# Audio_Cape_Guitar_Conversion.net
KiCad netlist of a schematic drawn in EAGLE
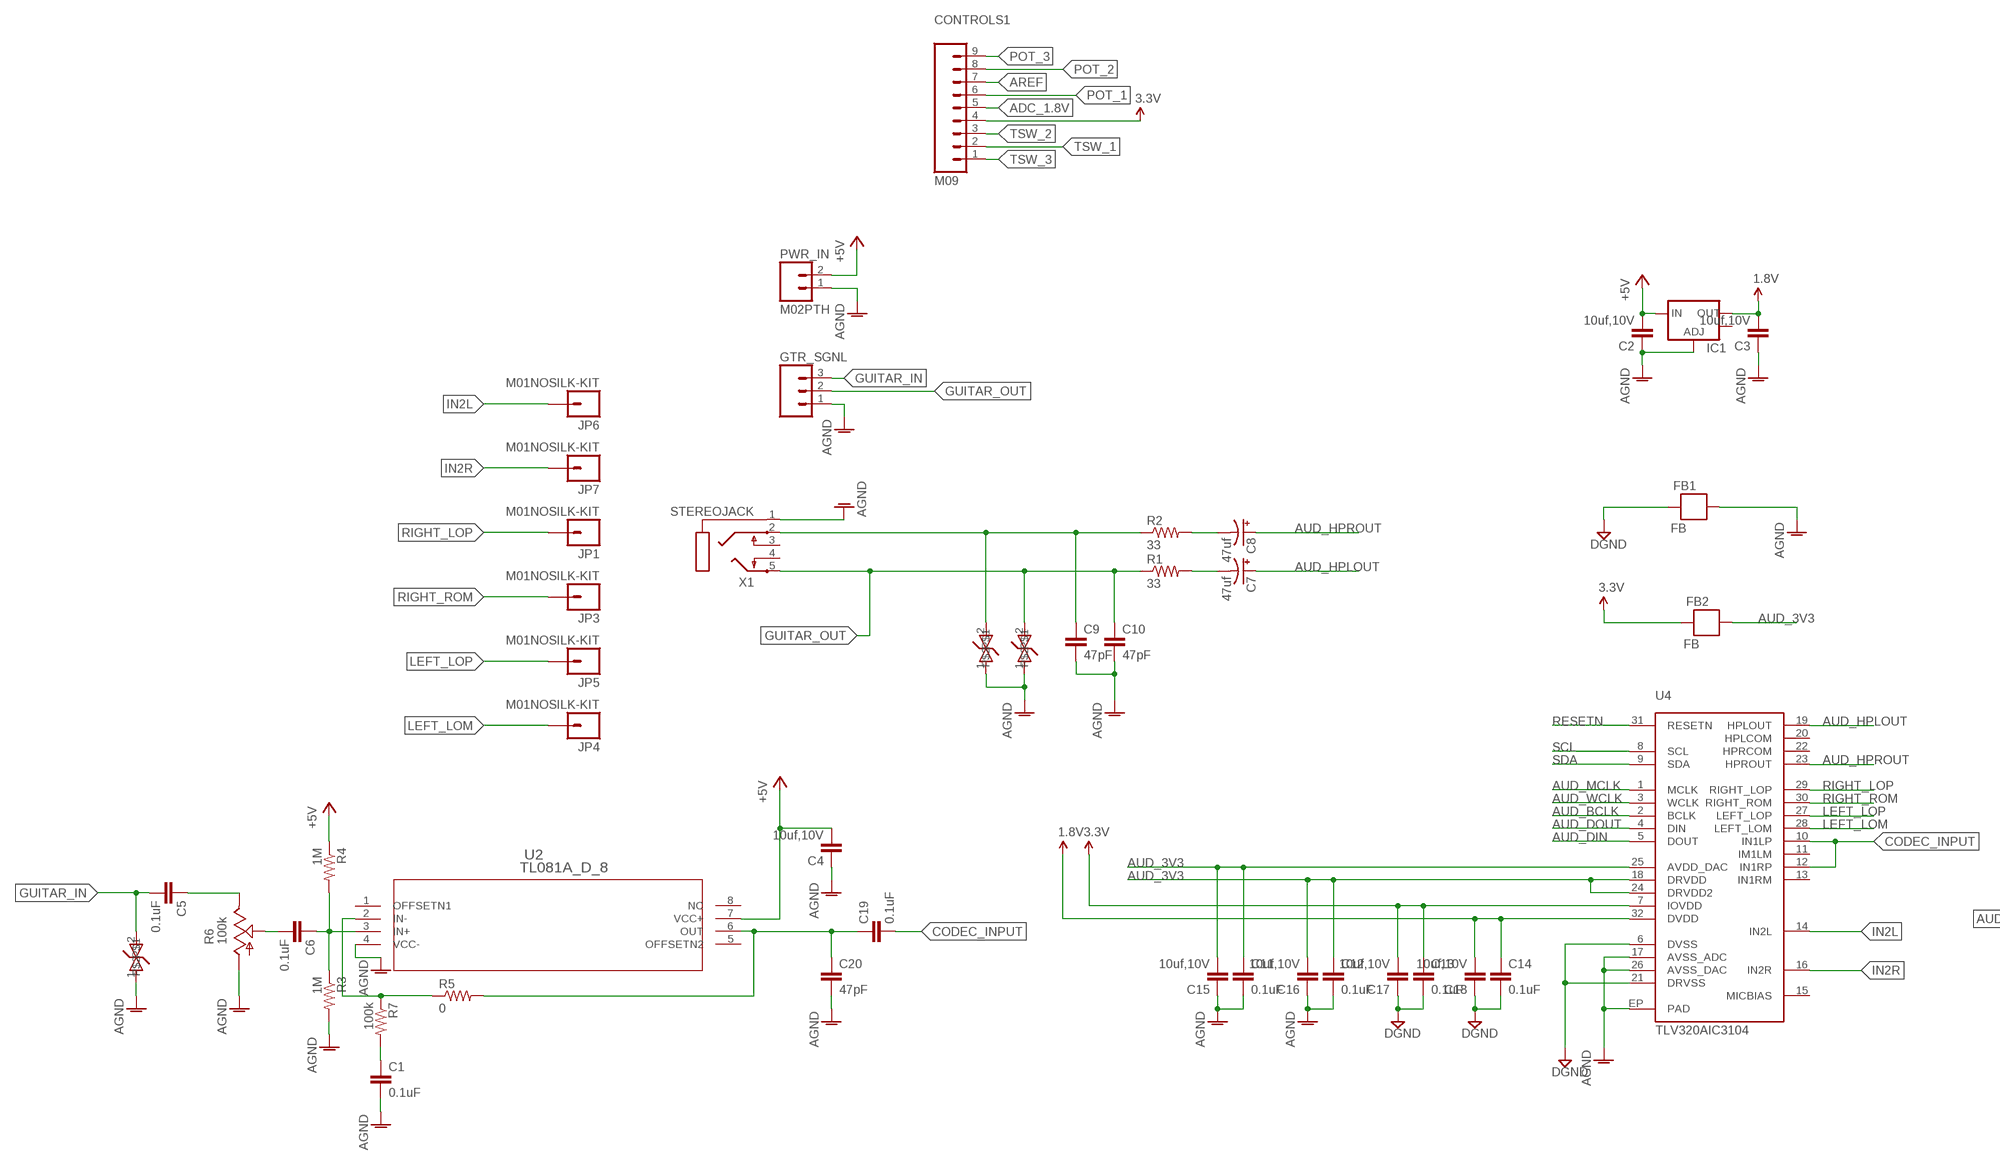
[diagram p0: schematic, sheet 1, part 1 of 2]
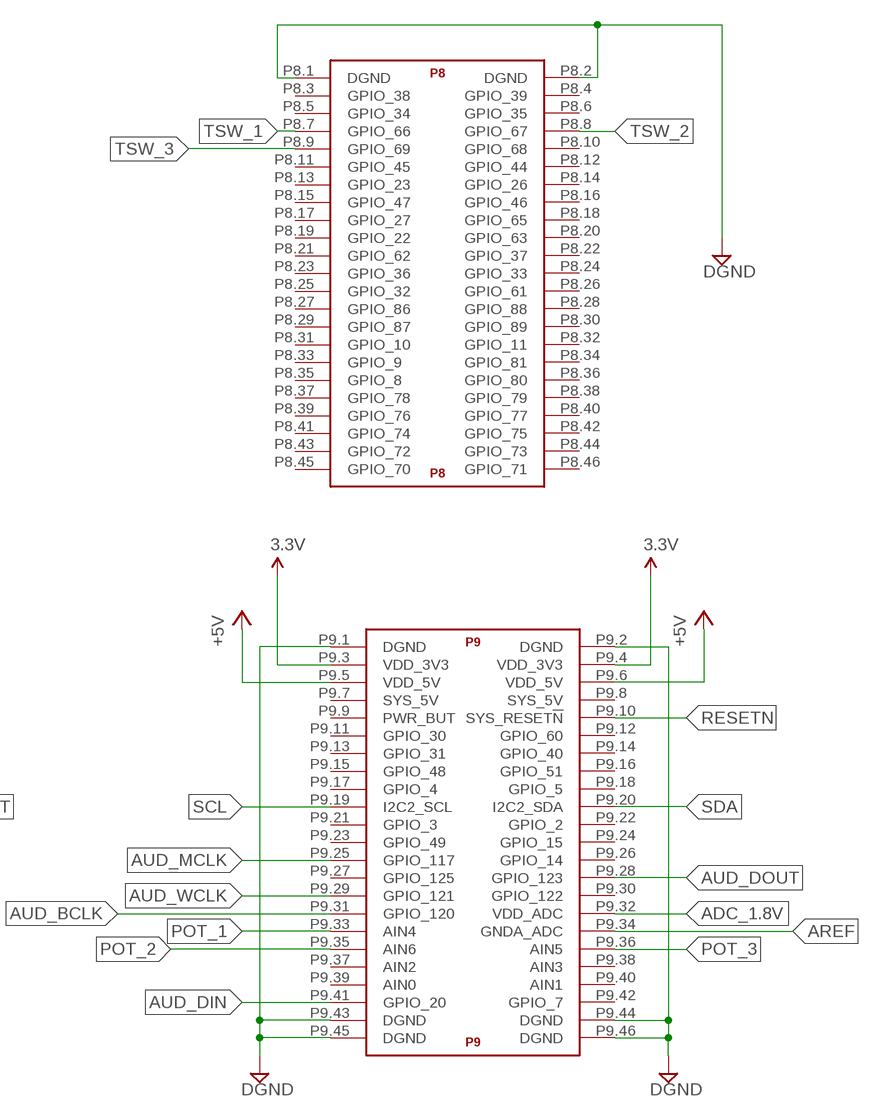
[diagram p1: schematic, sheet 1, part 2 of 2]

(export (version "E")
  (design (tool "Eeschema 10.0.6"))
  (components
    (comp (ref "C1")
      (value "0.1uF")
      (footprint "eagle-import:0603-CAP")
      (libsource (lib "eagle-import") (part "0.1UF-25V-5%(0603)"))
    )
    (comp (ref "C2")
      (value "10uf,10V")
      (footprint "eagle-import:0603-CAP")
      (libsource (lib "eagle-import") (part "CAP0603-CAP"))
    )
    (comp (ref "C3")
      (value "10uf,10V")
      (footprint "eagle-import:0603-CAP")
      (libsource (lib "eagle-import") (part "CAP0603-CAP"))
    )
    (comp (ref "C4")
      (value "10uf,10V")
      (footprint "eagle-import:0603-CAP")
      (libsource (lib "eagle-import") (part "CAP0603-CAP"))
    )
    (comp (ref "C5")
      (value "0.1uF")
      (footprint "eagle-import:0603-CAP")
      (libsource (lib "eagle-import") (part "0.1UF-25V-5%(0603)"))
    )
    (comp (ref "C6")
      (value "0.1uF")
      (footprint "eagle-import:0603-CAP")
      (libsource (lib "eagle-import") (part "0.1UF-25V-5%(0603)"))
    )
    (comp (ref "C7")
      (value "47uf")
      (footprint "eagle-import:EIA3216")
      (libsource (lib "eagle-import") (part "CAP_POL1206"))
    )
    (comp (ref "C8")
      (value "47uf")
      (footprint "eagle-import:EIA3216")
      (libsource (lib "eagle-import") (part "CAP_POL1206"))
    )
    (comp (ref "C9")
      (value "47pF")
      (footprint "eagle-import:0402-CAP")
      (libsource (lib "eagle-import") (part "CAP0402-CAP"))
    )
    (comp (ref "C10")
      (value "47pF")
      (footprint "eagle-import:0402-CAP")
      (libsource (lib "eagle-import") (part "CAP0402-CAP"))
    )
    (comp (ref "C11")
      (value "0.1uF")
      (footprint "eagle-import:0603-CAP")
      (libsource (lib "eagle-import") (part "0.1UF-25V-5%(0603)"))
    )
    (comp (ref "C12")
      (value "0.1uF")
      (footprint "eagle-import:0603-CAP")
      (libsource (lib "eagle-import") (part "0.1UF-25V-5%(0603)"))
    )
    (comp (ref "C13")
      (value "0.1uF")
      (footprint "eagle-import:0603-CAP")
      (libsource (lib "eagle-import") (part "0.1UF-25V-5%(0603)"))
    )
    (comp (ref "C14")
      (value "0.1uF")
      (footprint "eagle-import:0603-CAP")
      (libsource (lib "eagle-import") (part "0.1UF-25V-5%(0603)"))
    )
    (comp (ref "C15")
      (value "10uf,10V")
      (footprint "eagle-import:0603-CAP")
      (libsource (lib "eagle-import") (part "CAP0603-CAP"))
    )
    (comp (ref "C16")
      (value "10uf,10V")
      (footprint "eagle-import:0603-CAP")
      (libsource (lib "eagle-import") (part "CAP0603-CAP"))
    )
    (comp (ref "C17")
      (value "10uf,10V")
      (footprint "eagle-import:0603-CAP")
      (libsource (lib "eagle-import") (part "CAP0603-CAP"))
    )
    (comp (ref "C18")
      (value "10uf,10V")
      (footprint "eagle-import:0603-CAP")
      (libsource (lib "eagle-import") (part "CAP0603-CAP"))
    )
    (comp (ref "C19")
      (value "0.1uF")
      (footprint "eagle-import:0603-CAP")
      (libsource (lib "eagle-import") (part "0.1UF-25V-5%(0603)"))
    )
    (comp (ref "C20")
      (value "47pF")
      (footprint "eagle-import:0402-CAP")
      (libsource (lib "eagle-import") (part "CAP0402-CAP"))
    )
    (comp (ref "CONTROLS1")
      (value "M09")
      (footprint "eagle-import:1X09")
      (libsource (lib "eagle-import") (part "M09"))
    )
    (comp (ref "D1")
      (value "PGB0010603MR")
      (footprint "eagle-import:0603")
      (libsource (lib "eagle-import") (part "PGB0010603MR"))
    )
    (comp (ref "D2")
      (value "PGB0010603MR")
      (footprint "eagle-import:0603")
      (libsource (lib "eagle-import") (part "PGB0010603MR"))
    )
    (comp (ref "D3")
      (value "PGB0010603MR")
      (footprint "eagle-import:0603")
      (libsource (lib "eagle-import") (part "PGB0010603MR"))
    )
    (comp (ref "FB1")
      (value "FB")
      (footprint "eagle-import:0603")
      (libsource (lib "eagle-import") (part "FB"))
    )
    (comp (ref "FB2")
      (value "FB")
      (footprint "eagle-import:0603")
      (libsource (lib "eagle-import") (part "FB"))
    )
    (comp (ref "GTR_SGNL")
      (value "M03PTH")
      (footprint "eagle-import:1X03")
      (libsource (lib "eagle-import") (part "M03PTH"))
    )
    (comp (ref "IC1")
      (value "V_REG_LM1117SOT223")
      (footprint "eagle-import:SOT223")
      (libsource (lib "eagle-import") (part "V_REG_LM1117SOT223"))
    )
    (comp (ref "JP1")
      (value "M01NOSILK-KIT")
      (footprint "eagle-import:1X01NS-KIT")
      (libsource (lib "eagle-import") (part "M01NOSILK-KIT"))
    )
    (comp (ref "JP3")
      (value "M01NOSILK-KIT")
      (footprint "eagle-import:1X01NS-KIT")
      (libsource (lib "eagle-import") (part "M01NOSILK-KIT"))
    )
    (comp (ref "JP4")
      (value "M01NOSILK-KIT")
      (footprint "eagle-import:1X01NS-KIT")
      (libsource (lib "eagle-import") (part "M01NOSILK-KIT"))
    )
    (comp (ref "JP5")
      (value "M01NOSILK-KIT")
      (footprint "eagle-import:1X01NS-KIT")
      (libsource (lib "eagle-import") (part "M01NOSILK-KIT"))
    )
    (comp (ref "JP6")
      (value "M01NOSILK-KIT")
      (footprint "eagle-import:1X01NS-KIT")
      (libsource (lib "eagle-import") (part "M01NOSILK-KIT"))
    )
    (comp (ref "JP7")
      (value "M01NOSILK-KIT")
      (footprint "eagle-import:1X01NS-KIT")
      (libsource (lib "eagle-import") (part "M01NOSILK-KIT"))
    )
    (comp (ref "PWR_IN")
      (value "M02PTH")
      (footprint "eagle-import:1X02")
      (libsource (lib "eagle-import") (part "M02PTH"))
    )
    (comp (ref "R1")
      (value "33")
      (footprint "eagle-import:1206")
      (libsource (lib "eagle-import") (part "SparkFun-Resistors_RESISTOR1206"))
    )
    (comp (ref "R2")
      (value "33")
      (footprint "eagle-import:1206")
      (libsource (lib "eagle-import") (part "SparkFun-Resistors_RESISTOR1206"))
    )
    (comp (ref "R3")
      (value "1M")
      (footprint "eagle-import:1206")
      (libsource (lib "eagle-import") (part "SparkFun-Resistors_RESISTOR1206"))
    )
    (comp (ref "R4")
      (value "1M")
      (footprint "eagle-import:1206")
      (libsource (lib "eagle-import") (part "SparkFun-Resistors_RESISTOR1206"))
    )
    (comp (ref "R5")
      (value "0")
      (footprint "eagle-import:AXIAL-0.4")
      (libsource (lib "eagle-import") (part "RESISTORPTH-1/4W"))
    )
    (comp (ref "R6")
      (value "100k")
      (footprint "eagle-import:S64Y")
      (libsource (lib "eagle-import") (part "TRIM_US-S64Y"))
    )
    (comp (ref "R7")
      (value "100k")
      (footprint "eagle-import:1206")
      (libsource (lib "eagle-import") (part "SparkFun-Resistors_RESISTOR1206"))
    )
    (comp (ref "U$1")
      (value "BEAGLE_BONE_BLACK_CAPE")
      (footprint "eagle-import:BEAGLE_BONE_BLACK_CAPE")
      (libsource (lib "eagle-import") (part "BEAGLE_BONE_BLACK_CAPE"))
    )
    (comp (ref "U2")
      (value "TL081A_D_8")
      (footprint "eagle-import:D8")
      (fields
        (field (name "GENERIC_PART_NUMBER") "TL081A")
        (field (name "MANUFACTURER") "Texas Instruments")
        (field (name "MANUFACTURER_PART_NUMBER") "tl081a_d_8")
      )
      (libsource (lib "eagle-import") (part "TL081A_D_8"))
    )
    (comp (ref "U4")
      (value "TLV320AIC3104")
      (footprint "eagle-import:QFN-32")
      (libsource (lib "eagle-import") (part "TLV320AIC3104"))
    )
    (comp (ref "X1")
      (value "STEREOJACK")
      (footprint "eagle-import:STX3100")
      (libsource (lib "eagle-import") (part "STEREOJACK"))
    )
  )
  (nets
    (net (code "1") (name "+5V") (class "Default")
      (node (ref "C2") (pin "2") (pinfunction "2_2") (pintype "passive"))
      (node (ref "C4") (pin "2") (pinfunction "2_2") (pintype "passive"))
      (node (ref "IC1") (pin "3") (pinfunction "IN_3") (pintype "input"))
      (node (ref "PWR_IN") (pin "2") (pinfunction "2_2") (pintype "passive"))
      (node (ref "R4") (pin "1") (pinfunction "1_1") (pintype "passive"))
      (node (ref "U$1") (pin "P9.5") (pinfunction "VDD_5V_P9.5") (pintype "bidirectional"))
      (node (ref "U$1") (pin "P9.6") (pinfunction "VDD_5V_P9.6") (pintype "bidirectional"))
      (node (ref "U2") (pin "7") (pinfunction "VCC+_7") (pintype "power_in"))
    )
    (net (code "2") (name "/AUD_3V3") (class "Default")
      (node (ref "C11") (pin "1") (pinfunction "1_1") (pintype "passive"))
      (node (ref "C12") (pin "1") (pinfunction "1_1") (pintype "passive"))
      (node (ref "C15") (pin "2") (pinfunction "2_2") (pintype "passive"))
      (node (ref "C16") (pin "2") (pinfunction "2_2") (pintype "passive"))
      (node (ref "FB2") (pin "1") (pinfunction "P$1_1") (pintype "bidirectional"))
      (node (ref "U4") (pin "18") (pinfunction "DRVDD_18") (pintype "bidirectional"))
      (node (ref "U4") (pin "24") (pinfunction "DRVDD2_24") (pintype "bidirectional"))
      (node (ref "U4") (pin "25") (pinfunction "AVDD_DAC_25") (pintype "bidirectional"))
    )
    (net (code "3") (name "/AUD_HPLOUT") (class "Default")
      (node (ref "C7") (pin "A") (pinfunction "+_A") (pintype "passive"))
      (node (ref "U4") (pin "19") (pinfunction "HPLOUT_19") (pintype "bidirectional"))
    )
    (net (code "4") (name "/AUD_HPROUT") (class "Default")
      (node (ref "C8") (pin "A") (pinfunction "+_A") (pintype "passive"))
      (node (ref "U4") (pin "23") (pinfunction "HPROUT_23") (pintype "bidirectional"))
    )
    (net (code "5") (name "1.8V") (class "Default")
      (node (ref "C14") (pin "1") (pinfunction "1_1") (pintype "passive"))
      (node (ref "C18") (pin "2") (pinfunction "2_2") (pintype "passive"))
      (node (ref "C3") (pin "2") (pinfunction "2_2") (pintype "passive"))
      (node (ref "IC1") (pin "2") (pinfunction "OUT_2") (pintype "output"))
      (node (ref "U4") (pin "32") (pinfunction "DVDD_32") (pintype "bidirectional"))
    )
    (net (code "6") (name "3.3V") (class "Default")
      (node (ref "C13") (pin "1") (pinfunction "1_1") (pintype "passive"))
      (node (ref "C17") (pin "2") (pinfunction "2_2") (pintype "passive"))
      (node (ref "CONTROLS1") (pin "4") (pinfunction "4_4") (pintype "passive"))
      (node (ref "FB2") (pin "2") (pinfunction "P$2_2") (pintype "bidirectional"))
      (node (ref "U$1") (pin "P9.3") (pinfunction "VDD_3V3_P9.3") (pintype "bidirectional"))
      (node (ref "U$1") (pin "P9.4") (pinfunction "VDD_3V3_P9.4") (pintype "bidirectional"))
      (node (ref "U4") (pin "7") (pinfunction "IOVDD_7") (pintype "bidirectional"))
    )
    (net (code "7") (name "ADC_1.8V") (class "Default")
      (node (ref "CONTROLS1") (pin "5") (pinfunction "5_5") (pintype "passive"))
      (node (ref "U$1") (pin "P9.32") (pinfunction "VDD_ADC_P9.32") (pintype "bidirectional"))
    )
    (net (code "8") (name "AGND") (class "Default")
      (node (ref "C1") (pin "2") (pinfunction "2_2") (pintype "passive"))
      (node (ref "C10") (pin "2") (pinfunction "2_2") (pintype "passive"))
      (node (ref "C11") (pin "2") (pinfunction "2_2") (pintype "passive"))
      (node (ref "C12") (pin "2") (pinfunction "2_2") (pintype "passive"))
      (node (ref "C15") (pin "1") (pinfunction "1_1") (pintype "passive"))
      (node (ref "C16") (pin "1") (pinfunction "1_1") (pintype "passive"))
      (node (ref "C2") (pin "1") (pinfunction "1_1") (pintype "passive"))
      (node (ref "C20") (pin "2") (pinfunction "2_2") (pintype "passive"))
      (node (ref "C3") (pin "1") (pinfunction "1_1") (pintype "passive"))
      (node (ref "C4") (pin "1") (pinfunction "1_1") (pintype "passive"))
      (node (ref "C9") (pin "2") (pinfunction "2_2") (pintype "passive"))
      (node (ref "D1") (pin "1") (pinfunction "P$1_1") (pintype "bidirectional"))
      (node (ref "D2") (pin "1") (pinfunction "P$1_1") (pintype "bidirectional"))
      (node (ref "D3") (pin "1") (pinfunction "P$1_1") (pintype "bidirectional"))
      (node (ref "FB1") (pin "1") (pinfunction "P$1_1") (pintype "bidirectional"))
      (node (ref "GTR_SGNL") (pin "1") (pinfunction "1_1") (pintype "passive"))
      (node (ref "IC1") (pin "1") (pinfunction "ADJ_1") (pintype "input"))
      (node (ref "PWR_IN") (pin "1") (pinfunction "1_1") (pintype "passive"))
      (node (ref "R3") (pin "2") (pinfunction "2_2") (pintype "passive"))
      (node (ref "R6") (pin "A") (pinfunction "A_A") (pintype "passive"))
      (node (ref "U2") (pin "4") (pinfunction "VCC-_4") (pintype "power_in"))
      (node (ref "U4") (pin "17") (pinfunction "AVSS_ADC_17") (pintype "bidirectional"))
      (node (ref "U4") (pin "26") (pinfunction "AVSS_DAC_26") (pintype "bidirectional"))
      (node (ref "U4") (pin "EP") (pinfunction "PAD_EP") (pintype "bidirectional"))
      (node (ref "X1") (pin "1") (pinfunction "1_1") (pintype "passive"))
    )
    (net (code "9") (name "AREF") (class "Default")
      (node (ref "CONTROLS1") (pin "7") (pinfunction "7_7") (pintype "passive"))
      (node (ref "U$1") (pin "P9.34") (pinfunction "GNDA_ADC_P9.34") (pintype "bidirectional"))
    )
    (net (code "10") (name "AUD_BCLK") (class "Default")
      (node (ref "U$1") (pin "P9.31") (pinfunction "GPIO_120_P9.31") (pintype "bidirectional"))
      (node (ref "U4") (pin "2") (pinfunction "BCLK_2") (pintype "bidirectional"))
    )
    (net (code "11") (name "AUD_DIN") (class "Default")
      (node (ref "U$1") (pin "P9.41") (pinfunction "GPIO_20_P9.41") (pintype "bidirectional"))
      (node (ref "U4") (pin "5") (pinfunction "DOUT_5") (pintype "bidirectional"))
    )
    (net (code "12") (name "AUD_DOUT") (class "Default")
      (node (ref "U$1") (pin "P9.28") (pinfunction "GPIO_123_P9.28") (pintype "bidirectional"))
      (node (ref "U4") (pin "4") (pinfunction "DIN_4") (pintype "bidirectional"))
    )
    (net (code "13") (name "AUD_MCLK") (class "Default")
      (node (ref "U$1") (pin "P9.25") (pinfunction "GPIO_117_P9.25") (pintype "bidirectional"))
      (node (ref "U4") (pin "1") (pinfunction "MCLK_1") (pintype "bidirectional"))
    )
    (net (code "14") (name "AUD_WCLK") (class "Default")
      (node (ref "U$1") (pin "P9.29") (pinfunction "GPIO_121_P9.29") (pintype "bidirectional"))
      (node (ref "U4") (pin "3") (pinfunction "WCLK_3") (pintype "bidirectional"))
    )
    (net (code "15") (name "CODEC_INPUT") (class "Default")
      (node (ref "C19") (pin "2") (pinfunction "2_2") (pintype "passive"))
      (node (ref "U4") (pin "10") (pinfunction "IN1LP_10") (pintype "bidirectional"))
      (node (ref "U4") (pin "12") (pinfunction "IN1RP_12") (pintype "bidirectional"))
    )
    (net (code "16") (name "DGND") (class "Default")
      (node (ref "C13") (pin "2") (pinfunction "2_2") (pintype "passive"))
      (node (ref "C14") (pin "2") (pinfunction "2_2") (pintype "passive"))
      (node (ref "C17") (pin "1") (pinfunction "1_1") (pintype "passive"))
      (node (ref "C18") (pin "1") (pinfunction "1_1") (pintype "passive"))
      (node (ref "FB1") (pin "2") (pinfunction "P$2_2") (pintype "bidirectional"))
      (node (ref "U$1") (pin "P8.1") (pinfunction "DGND_P8.1") (pintype "bidirectional"))
      (node (ref "U$1") (pin "P8.2") (pinfunction "DGND_P8.2") (pintype "bidirectional"))
      (node (ref "U$1") (pin "P9.1") (pinfunction "DGND_P9.1") (pintype "bidirectional"))
      (node (ref "U$1") (pin "P9.2") (pinfunction "DGND_P9.2") (pintype "bidirectional"))
      (node (ref "U$1") (pin "P9.43") (pinfunction "DGND_P9.43") (pintype "bidirectional"))
      (node (ref "U$1") (pin "P9.44") (pinfunction "DGND_P9.44") (pintype "bidirectional"))
      (node (ref "U$1") (pin "P9.45") (pinfunction "DGND_P9.45") (pintype "bidirectional"))
      (node (ref "U$1") (pin "P9.46") (pinfunction "DGND_P9.46") (pintype "bidirectional"))
      (node (ref "U4") (pin "21") (pinfunction "DRVSS_21") (pintype "bidirectional"))
      (node (ref "U4") (pin "6") (pinfunction "DVSS_6") (pintype "bidirectional"))
    )
    (net (code "17") (name "GUITAR_IN") (class "Default")
      (node (ref "C5") (pin "2") (pinfunction "2_2") (pintype "passive"))
      (node (ref "D3") (pin "2") (pinfunction "P$2_2") (pintype "bidirectional"))
      (node (ref "GTR_SGNL") (pin "3") (pinfunction "3_3") (pintype "passive"))
    )
    (net (code "18") (name "GUITAR_OUT") (class "Default")
      (node (ref "C10") (pin "1") (pinfunction "1_1") (pintype "passive"))
      (node (ref "D2") (pin "2") (pinfunction "P$2_2") (pintype "bidirectional"))
      (node (ref "GTR_SGNL") (pin "2") (pinfunction "2_2") (pintype "passive"))
      (node (ref "R1") (pin "1") (pinfunction "1_1") (pintype "passive"))
      (node (ref "X1") (pin "5") (pinfunction "5_5") (pintype "passive"))
    )
    (net (code "19") (name "IN2L") (class "Default")
      (node (ref "JP6") (pin "1") (pinfunction "1_1") (pintype "passive"))
      (node (ref "U4") (pin "14") (pinfunction "IN2L_14") (pintype "bidirectional"))
    )
    (net (code "20") (name "IN2R") (class "Default")
      (node (ref "JP7") (pin "1") (pinfunction "1_1") (pintype "passive"))
      (node (ref "U4") (pin "16") (pinfunction "IN2R_16") (pintype "bidirectional"))
    )
    (net (code "21") (name "LEFT_LOM") (class "Default")
      (node (ref "JP4") (pin "1") (pinfunction "1_1") (pintype "passive"))
      (node (ref "U4") (pin "28") (pinfunction "LEFT_LOM_28") (pintype "bidirectional"))
    )
    (net (code "22") (name "LEFT_LOP") (class "Default")
      (node (ref "JP5") (pin "1") (pinfunction "1_1") (pintype "passive"))
      (node (ref "U4") (pin "27") (pinfunction "LEFT_LOP_27") (pintype "bidirectional"))
    )
    (net (code "23") (name "Net-(C1-Pad1)") (class "Default")
      (node (ref "C1") (pin "1") (pinfunction "1_1") (pintype "passive"))
      (node (ref "R7") (pin "2") (pinfunction "2_2") (pintype "passive"))
    )
    (net (code "24") (name "Net-(C5-Pad1)") (class "Default")
      (node (ref "C5") (pin "1") (pinfunction "1_1") (pintype "passive"))
      (node (ref "R6") (pin "E") (pinfunction "E_E") (pintype "passive"))
    )
    (net (code "25") (name "Net-(C6-Pad2)") (class "Default")
      (node (ref "C6") (pin "2") (pinfunction "2_2") (pintype "passive"))
      (node (ref "R6") (pin "S") (pinfunction "S_S") (pintype "passive"))
    )
    (net (code "26") (name "Net-(C7--)") (class "Default")
      (node (ref "C7") (pin "C") (pinfunction "-_C") (pintype "passive"))
      (node (ref "R1") (pin "2") (pinfunction "2_2") (pintype "passive"))
    )
    (net (code "27") (name "Net-(C8--)") (class "Default")
      (node (ref "C8") (pin "C") (pinfunction "-_C") (pintype "passive"))
      (node (ref "R2") (pin "2") (pinfunction "2_2") (pintype "passive"))
    )
    (net (code "28") (name "Net-(D1-P$2)") (class "Default")
      (node (ref "C9") (pin "1") (pinfunction "1_1") (pintype "passive"))
      (node (ref "D1") (pin "2") (pinfunction "P$2_2") (pintype "bidirectional"))
      (node (ref "R2") (pin "1") (pinfunction "1_1") (pintype "passive"))
      (node (ref "X1") (pin "2") (pinfunction "2_2") (pintype "passive"))
    )
    (net (code "29") (name "Net-(R5-1)") (class "Default")
      (node (ref "R5") (pin "P$1") (pinfunction "1_P$1") (pintype "passive"))
      (node (ref "R7") (pin "1") (pinfunction "1_1") (pintype "passive"))
      (node (ref "U2") (pin "2") (pinfunction "IN-_2") (pintype "input"))
    )
    (net (code "30") (name "Net-(R5-2)") (class "Default")
      (node (ref "C19") (pin "1") (pinfunction "1_1") (pintype "passive"))
      (node (ref "C20") (pin "1") (pinfunction "1_1") (pintype "passive"))
      (node (ref "R5") (pin "P$2") (pinfunction "2_P$2") (pintype "passive"))
      (node (ref "U2") (pin "6") (pinfunction "OUT_6") (pintype "output"))
    )
    (net (code "31") (name "Net-(U2-IN+)") (class "Default")
      (node (ref "C6") (pin "1") (pinfunction "1_1") (pintype "passive"))
      (node (ref "R3") (pin "1") (pinfunction "1_1") (pintype "passive"))
      (node (ref "R4") (pin "2") (pinfunction "2_2") (pintype "passive"))
      (node (ref "U2") (pin "3") (pinfunction "IN+_3") (pintype "input"))
    )
    (net (code "32") (name "POT_1") (class "Default")
      (node (ref "CONTROLS1") (pin "6") (pinfunction "6_6") (pintype "passive"))
      (node (ref "U$1") (pin "P9.33") (pinfunction "AIN4_P9.33") (pintype "bidirectional"))
    )
    (net (code "33") (name "POT_2") (class "Default")
      (node (ref "CONTROLS1") (pin "8") (pinfunction "8_8") (pintype "passive"))
      (node (ref "U$1") (pin "P9.35") (pinfunction "AIN6_P9.35") (pintype "bidirectional"))
    )
    (net (code "34") (name "POT_3") (class "Default")
      (node (ref "CONTROLS1") (pin "9") (pinfunction "9_9") (pintype "passive"))
      (node (ref "U$1") (pin "P9.36") (pinfunction "AIN5_P9.36") (pintype "bidirectional"))
    )
    (net (code "35") (name "RESETN") (class "Default")
      (node (ref "U$1") (pin "P9.10") (pinfunction "SYS_RESET~{N}_P9.10") (pintype "bidirectional"))
      (node (ref "U4") (pin "31") (pinfunction "RESETN_31") (pintype "bidirectional"))
    )
    (net (code "36") (name "RIGHT_LOP") (class "Default")
      (node (ref "JP1") (pin "1") (pinfunction "1_1") (pintype "passive"))
      (node (ref "U4") (pin "29") (pinfunction "RIGHT_LOP_29") (pintype "bidirectional"))
    )
    (net (code "37") (name "RIGHT_ROM") (class "Default")
      (node (ref "JP3") (pin "1") (pinfunction "1_1") (pintype "passive"))
      (node (ref "U4") (pin "30") (pinfunction "RIGHT_ROM_30") (pintype "bidirectional"))
    )
    (net (code "38") (name "SCL") (class "Default")
      (node (ref "U$1") (pin "P9.19") (pinfunction "I2C2_SCL_P9.19") (pintype "bidirectional"))
      (node (ref "U4") (pin "8") (pinfunction "SCL_8") (pintype "bidirectional"))
    )
    (net (code "39") (name "SDA") (class "Default")
      (node (ref "U$1") (pin "P9.20") (pinfunction "I2C2_SDA_P9.20") (pintype "bidirectional"))
      (node (ref "U4") (pin "9") (pinfunction "SDA_9") (pintype "bidirectional"))
    )
    (net (code "40") (name "TSW_1") (class "Default")
      (node (ref "CONTROLS1") (pin "2") (pinfunction "2_2") (pintype "passive"))
      (node (ref "U$1") (pin "P8.7") (pinfunction "GPIO_66_P8.7") (pintype "bidirectional"))
    )
    (net (code "41") (name "TSW_2") (class "Default")
      (node (ref "CONTROLS1") (pin "3") (pinfunction "3_3") (pintype "passive"))
      (node (ref "U$1") (pin "P8.8") (pinfunction "GPIO_67_P8.8") (pintype "bidirectional"))
    )
    (net (code "42") (name "TSW_3") (class "Default")
      (node (ref "CONTROLS1") (pin "1") (pinfunction "1_1") (pintype "passive"))
      (node (ref "U$1") (pin "P8.9") (pinfunction "GPIO_69_P8.9") (pintype "bidirectional"))
    )
    (net (code "43") (name "unconnected-(IC1-OUT-Pad4)") (class "Default")
      (node (ref "IC1") (pin "4") (pinfunction "OUT_4") (pintype "output"))
    )
    (net (code "44") (name "unconnected-(U$1A-GPIO_8-PadP8.35)") (class "Default")
      (node (ref "U$1") (pin "P8.35") (pinfunction "GPIO_8_P8.35") (pintype "bidirectional"))
    )
    (net (code "45") (name "unconnected-(U$1A-GPIO_9-PadP8.33)") (class "Default")
      (node (ref "U$1") (pin "P8.33") (pinfunction "GPIO_9_P8.33") (pintype "bidirectional"))
    )
    (net (code "46") (name "unconnected-(U$1A-GPIO_10-PadP8.31)") (class "Default")
      (node (ref "U$1") (pin "P8.31") (pinfunction "GPIO_10_P8.31") (pintype "bidirectional"))
    )
    (net (code "47") (name "unconnected-(U$1A-GPIO_11-PadP8.32)") (class "Default")
      (node (ref "U$1") (pin "P8.32") (pinfunction "GPIO_11_P8.32") (pintype "bidirectional"))
    )
    (net (code "48") (name "unconnected-(U$1A-GPIO_22-PadP8.19)") (class "Default")
      (node (ref "U$1") (pin "P8.19") (pinfunction "GPIO_22_P8.19") (pintype "bidirectional"))
    )
    (net (code "49") (name "unconnected-(U$1A-GPIO_23-PadP8.13)") (class "Default")
      (node (ref "U$1") (pin "P8.13") (pinfunction "GPIO_23_P8.13") (pintype "bidirectional"))
    )
    (net (code "50") (name "unconnected-(U$1A-GPIO_26-PadP8.14)") (class "Default")
      (node (ref "U$1") (pin "P8.14") (pinfunction "GPIO_26_P8.14") (pintype "bidirectional"))
    )
    (net (code "51") (name "unconnected-(U$1A-GPIO_27-PadP8.17)") (class "Default")
      (node (ref "U$1") (pin "P8.17") (pinfunction "GPIO_27_P8.17") (pintype "bidirectional"))
    )
    (net (code "52") (name "unconnected-(U$1A-GPIO_32-PadP8.25)") (class "Default")
      (node (ref "U$1") (pin "P8.25") (pinfunction "GPIO_32_P8.25") (pintype "bidirectional"))
    )
    (net (code "53") (name "unconnected-(U$1A-GPIO_33-PadP8.24)") (class "Default")
      (node (ref "U$1") (pin "P8.24") (pinfunction "GPIO_33_P8.24") (pintype "bidirectional"))
    )
    (net (code "54") (name "unconnected-(U$1A-GPIO_34-PadP8.5)") (class "Default")
      (node (ref "U$1") (pin "P8.5") (pinfunction "GPIO_34_P8.5") (pintype "bidirectional"))
    )
    (net (code "55") (name "unconnected-(U$1A-GPIO_35-PadP8.6)") (class "Default")
      (node (ref "U$1") (pin "P8.6") (pinfunction "GPIO_35_P8.6") (pintype "bidirectional"))
    )
    (net (code "56") (name "unconnected-(U$1A-GPIO_36-PadP8.23)") (class "Default")
      (node (ref "U$1") (pin "P8.23") (pinfunction "GPIO_36_P8.23") (pintype "bidirectional"))
    )
    (net (code "57") (name "unconnected-(U$1A-GPIO_37-PadP8.22)") (class "Default")
      (node (ref "U$1") (pin "P8.22") (pinfunction "GPIO_37_P8.22") (pintype "bidirectional"))
    )
    (net (code "58") (name "unconnected-(U$1A-GPIO_38-PadP8.3)") (class "Default")
      (node (ref "U$1") (pin "P8.3") (pinfunction "GPIO_38_P8.3") (pintype "bidirectional"))
    )
    (net (code "59") (name "unconnected-(U$1A-GPIO_39-PadP8.4)") (class "Default")
      (node (ref "U$1") (pin "P8.4") (pinfunction "GPIO_39_P8.4") (pintype "bidirectional"))
    )
    (net (code "60") (name "unconnected-(U$1A-GPIO_44-PadP8.12)") (class "Default")
      (node (ref "U$1") (pin "P8.12") (pinfunction "GPIO_44_P8.12") (pintype "bidirectional"))
    )
    (net (code "61") (name "unconnected-(U$1A-GPIO_45-PadP8.11)") (class "Default")
      (node (ref "U$1") (pin "P8.11") (pinfunction "GPIO_45_P8.11") (pintype "bidirectional"))
    )
    (net (code "62") (name "unconnected-(U$1A-GPIO_46-PadP8.16)") (class "Default")
      (node (ref "U$1") (pin "P8.16") (pinfunction "GPIO_46_P8.16") (pintype "bidirectional"))
    )
    (net (code "63") (name "unconnected-(U$1A-GPIO_47-PadP8.15)") (class "Default")
      (node (ref "U$1") (pin "P8.15") (pinfunction "GPIO_47_P8.15") (pintype "bidirectional"))
    )
    (net (code "64") (name "unconnected-(U$1A-GPIO_61-PadP8.26)") (class "Default")
      (node (ref "U$1") (pin "P8.26") (pinfunction "GPIO_61_P8.26") (pintype "bidirectional"))
    )
    (net (code "65") (name "unconnected-(U$1A-GPIO_62-PadP8.21)") (class "Default")
      (node (ref "U$1") (pin "P8.21") (pinfunction "GPIO_62_P8.21") (pintype "bidirectional"))
    )
    (net (code "66") (name "unconnected-(U$1A-GPIO_63-PadP8.20)") (class "Default")
      (node (ref "U$1") (pin "P8.20") (pinfunction "GPIO_63_P8.20") (pintype "bidirectional"))
    )
    (net (code "67") (name "unconnected-(U$1A-GPIO_65-PadP8.18)") (class "Default")
      (node (ref "U$1") (pin "P8.18") (pinfunction "GPIO_65_P8.18") (pintype "bidirectional"))
    )
    (net (code "68") (name "unconnected-(U$1A-GPIO_68-PadP8.10)") (class "Default")
      (node (ref "U$1") (pin "P8.10") (pinfunction "GPIO_68_P8.10") (pintype "bidirectional"))
    )
    (net (code "69") (name "unconnected-(U$1A-GPIO_70-PadP8.45)") (class "Default")
      (node (ref "U$1") (pin "P8.45") (pinfunction "GPIO_70_P8.45") (pintype "bidirectional"))
    )
    (net (code "70") (name "unconnected-(U$1A-GPIO_71-PadP8.46)") (class "Default")
      (node (ref "U$1") (pin "P8.46") (pinfunction "GPIO_71_P8.46") (pintype "bidirectional"))
    )
    (net (code "71") (name "unconnected-(U$1A-GPIO_72-PadP8.43)") (class "Default")
      (node (ref "U$1") (pin "P8.43") (pinfunction "GPIO_72_P8.43") (pintype "bidirectional"))
    )
    (net (code "72") (name "unconnected-(U$1A-GPIO_73-PadP8.44)") (class "Default")
      (node (ref "U$1") (pin "P8.44") (pinfunction "GPIO_73_P8.44") (pintype "bidirectional"))
    )
    (net (code "73") (name "unconnected-(U$1A-GPIO_74-PadP8.41)") (class "Default")
      (node (ref "U$1") (pin "P8.41") (pinfunction "GPIO_74_P8.41") (pintype "bidirectional"))
    )
    (net (code "74") (name "unconnected-(U$1A-GPIO_75-PadP8.42)") (class "Default")
      (node (ref "U$1") (pin "P8.42") (pinfunction "GPIO_75_P8.42") (pintype "bidirectional"))
    )
    (net (code "75") (name "unconnected-(U$1A-GPIO_76-PadP8.39)") (class "Default")
      (node (ref "U$1") (pin "P8.39") (pinfunction "GPIO_76_P8.39") (pintype "bidirectional"))
    )
    (net (code "76") (name "unconnected-(U$1A-GPIO_77-PadP8.40)") (class "Default")
      (node (ref "U$1") (pin "P8.40") (pinfunction "GPIO_77_P8.40") (pintype "bidirectional"))
    )
    (net (code "77") (name "unconnected-(U$1A-GPIO_78-PadP8.37)") (class "Default")
      (node (ref "U$1") (pin "P8.37") (pinfunction "GPIO_78_P8.37") (pintype "bidirectional"))
    )
    (net (code "78") (name "unconnected-(U$1A-GPIO_79-PadP8.38)") (class "Default")
      (node (ref "U$1") (pin "P8.38") (pinfunction "GPIO_79_P8.38") (pintype "bidirectional"))
    )
    (net (code "79") (name "unconnected-(U$1A-GPIO_80-PadP8.36)") (class "Default")
      (node (ref "U$1") (pin "P8.36") (pinfunction "GPIO_80_P8.36") (pintype "bidirectional"))
    )
    (net (code "80") (name "unconnected-(U$1A-GPIO_81-PadP8.34)") (class "Default")
      (node (ref "U$1") (pin "P8.34") (pinfunction "GPIO_81_P8.34") (pintype "bidirectional"))
    )
    (net (code "81") (name "unconnected-(U$1A-GPIO_86-PadP8.27)") (class "Default")
      (node (ref "U$1") (pin "P8.27") (pinfunction "GPIO_86_P8.27") (pintype "bidirectional"))
    )
    (net (code "82") (name "unconnected-(U$1A-GPIO_87-PadP8.29)") (class "Default")
      (node (ref "U$1") (pin "P8.29") (pinfunction "GPIO_87_P8.29") (pintype "bidirectional"))
    )
    (net (code "83") (name "unconnected-(U$1A-GPIO_88-PadP8.28)") (class "Default")
      (node (ref "U$1") (pin "P8.28") (pinfunction "GPIO_88_P8.28") (pintype "bidirectional"))
    )
    (net (code "84") (name "unconnected-(U$1A-GPIO_89-PadP8.30)") (class "Default")
      (node (ref "U$1") (pin "P8.30") (pinfunction "GPIO_89_P8.30") (pintype "bidirectional"))
    )
    (net (code "85") (name "unconnected-(U$1B-AIN0-PadP9.39)") (class "Default")
      (node (ref "U$1") (pin "P9.39") (pinfunction "AIN0_P9.39") (pintype "bidirectional"))
    )
    (net (code "86") (name "unconnected-(U$1B-AIN1-PadP9.40)") (class "Default")
      (node (ref "U$1") (pin "P9.40") (pinfunction "AIN1_P9.40") (pintype "bidirectional"))
    )
    (net (code "87") (name "unconnected-(U$1B-AIN2-PadP9.37)") (class "Default")
      (node (ref "U$1") (pin "P9.37") (pinfunction "AIN2_P9.37") (pintype "bidirectional"))
    )
    (net (code "88") (name "unconnected-(U$1B-AIN3-PadP9.38)") (class "Default")
      (node (ref "U$1") (pin "P9.38") (pinfunction "AIN3_P9.38") (pintype "bidirectional"))
    )
    (net (code "89") (name "unconnected-(U$1B-GPIO_2-PadP9.22)") (class "Default")
      (node (ref "U$1") (pin "P9.22") (pinfunction "GPIO_2_P9.22") (pintype "bidirectional"))
    )
    (net (code "90") (name "unconnected-(U$1B-GPIO_3-PadP9.21)") (class "Default")
      (node (ref "U$1") (pin "P9.21") (pinfunction "GPIO_3_P9.21") (pintype "bidirectional"))
    )
    (net (code "91") (name "unconnected-(U$1B-GPIO_4-PadP9.17)") (class "Default")
      (node (ref "U$1") (pin "P9.17") (pinfunction "GPIO_4_P9.17") (pintype "bidirectional"))
    )
    (net (code "92") (name "unconnected-(U$1B-GPIO_5-PadP9.18)") (class "Default")
      (node (ref "U$1") (pin "P9.18") (pinfunction "GPIO_5_P9.18") (pintype "bidirectional"))
    )
    (net (code "93") (name "unconnected-(U$1B-GPIO_7-PadP9.42)") (class "Default")
      (node (ref "U$1") (pin "P9.42") (pinfunction "GPIO_7_P9.42") (pintype "bidirectional"))
    )
    (net (code "94") (name "unconnected-(U$1B-GPIO_14-PadP9.26)") (class "Default")
      (node (ref "U$1") (pin "P9.26") (pinfunction "GPIO_14_P9.26") (pintype "bidirectional"))
    )
    (net (code "95") (name "unconnected-(U$1B-GPIO_15-PadP9.24)") (class "Default")
      (node (ref "U$1") (pin "P9.24") (pinfunction "GPIO_15_P9.24") (pintype "bidirectional"))
    )
    (net (code "96") (name "unconnected-(U$1B-GPIO_30-PadP9.11)") (class "Default")
      (node (ref "U$1") (pin "P9.11") (pinfunction "GPIO_30_P9.11") (pintype "bidirectional"))
    )
    (net (code "97") (name "unconnected-(U$1B-GPIO_31-PadP9.13)") (class "Default")
      (node (ref "U$1") (pin "P9.13") (pinfunction "GPIO_31_P9.13") (pintype "bidirectional"))
    )
    (net (code "98") (name "unconnected-(U$1B-GPIO_40-PadP9.14)") (class "Default")
      (node (ref "U$1") (pin "P9.14") (pinfunction "GPIO_40_P9.14") (pintype "bidirectional"))
    )
    (net (code "99") (name "unconnected-(U$1B-GPIO_48-PadP9.15)") (class "Default")
      (node (ref "U$1") (pin "P9.15") (pinfunction "GPIO_48_P9.15") (pintype "bidirectional"))
    )
    (net (code "100") (name "unconnected-(U$1B-GPIO_49-PadP9.23)") (class "Default")
      (node (ref "U$1") (pin "P9.23") (pinfunction "GPIO_49_P9.23") (pintype "bidirectional"))
    )
    (net (code "101") (name "unconnected-(U$1B-GPIO_51-PadP9.16)") (class "Default")
      (node (ref "U$1") (pin "P9.16") (pinfunction "GPIO_51_P9.16") (pintype "bidirectional"))
    )
    (net (code "102") (name "unconnected-(U$1B-GPIO_60-PadP9.12)") (class "Default")
      (node (ref "U$1") (pin "P9.12") (pinfunction "GPIO_60_P9.12") (pintype "bidirectional"))
    )
    (net (code "103") (name "unconnected-(U$1B-GPIO_122-PadP9.30)") (class "Default")
      (node (ref "U$1") (pin "P9.30") (pinfunction "GPIO_122_P9.30") (pintype "bidirectional"))
    )
    (net (code "104") (name "unconnected-(U$1B-GPIO_125-PadP9.27)") (class "Default")
      (node (ref "U$1") (pin "P9.27") (pinfunction "GPIO_125_P9.27") (pintype "bidirectional"))
    )
    (net (code "105") (name "unconnected-(U$1B-PWR_BUT-PadP9.9)") (class "Default")
      (node (ref "U$1") (pin "P9.9") (pinfunction "PWR_BUT_P9.9") (pintype "bidirectional"))
    )
    (net (code "106") (name "unconnected-(U$1B-SYS_5V-PadP9.7)") (class "Default")
      (node (ref "U$1") (pin "P9.7") (pinfunction "SYS_5V_P9.7") (pintype "bidirectional"))
    )
    (net (code "107") (name "unconnected-(U$1B-SYS_5V-PadP9.8)") (class "Default")
      (node (ref "U$1") (pin "P9.8") (pinfunction "SYS_5V_P9.8") (pintype "bidirectional"))
    )
    (net (code "108") (name "unconnected-(U2-NC-Pad8)") (class "Default")
      (node (ref "U2") (pin "8") (pinfunction "NC_8") (pintype "passive"))
    )
    (net (code "109") (name "unconnected-(U2-OFFSETN1-Pad1)") (class "Default")
      (node (ref "U2") (pin "1") (pinfunction "OFFSETN1_1") (pintype "passive"))
    )
    (net (code "110") (name "unconnected-(U2-OFFSETN2-Pad5)") (class "Default")
      (node (ref "U2") (pin "5") (pinfunction "OFFSETN2_5") (pintype "passive"))
    )
    (net (code "111") (name "unconnected-(U4-HPLCOM-Pad20)") (class "Default")
      (node (ref "U4") (pin "20") (pinfunction "HPLCOM_20") (pintype "bidirectional"))
    )
    (net (code "112") (name "unconnected-(U4-HPRCOM-Pad22)") (class "Default")
      (node (ref "U4") (pin "22") (pinfunction "HPRCOM_22") (pintype "bidirectional"))
    )
    (net (code "113") (name "unconnected-(U4-IM1LM-Pad11)") (class "Default")
      (node (ref "U4") (pin "11") (pinfunction "IM1LM_11") (pintype "bidirectional"))
    )
    (net (code "114") (name "unconnected-(U4-IN1RM-Pad13)") (class "Default")
      (node (ref "U4") (pin "13") (pinfunction "IN1RM_13") (pintype "bidirectional"))
    )
    (net (code "115") (name "unconnected-(U4-MICBIAS-Pad15)") (class "Default")
      (node (ref "U4") (pin "15") (pinfunction "MICBIAS_15") (pintype "bidirectional"))
    )
    (net (code "116") (name "unconnected-(X1-Pad3)") (class "Default")
      (node (ref "X1") (pin "3") (pinfunction "3_3") (pintype "passive"))
    )
    (net (code "117") (name "unconnected-(X1-Pad4)") (class "Default")
      (node (ref "X1") (pin "4") (pinfunction "4_4") (pintype "passive"))
    )
  )
)
